# SCH_USB-Hub_2025-03-01.net
KiCad netlist of a schematic drawn in EasyEDA
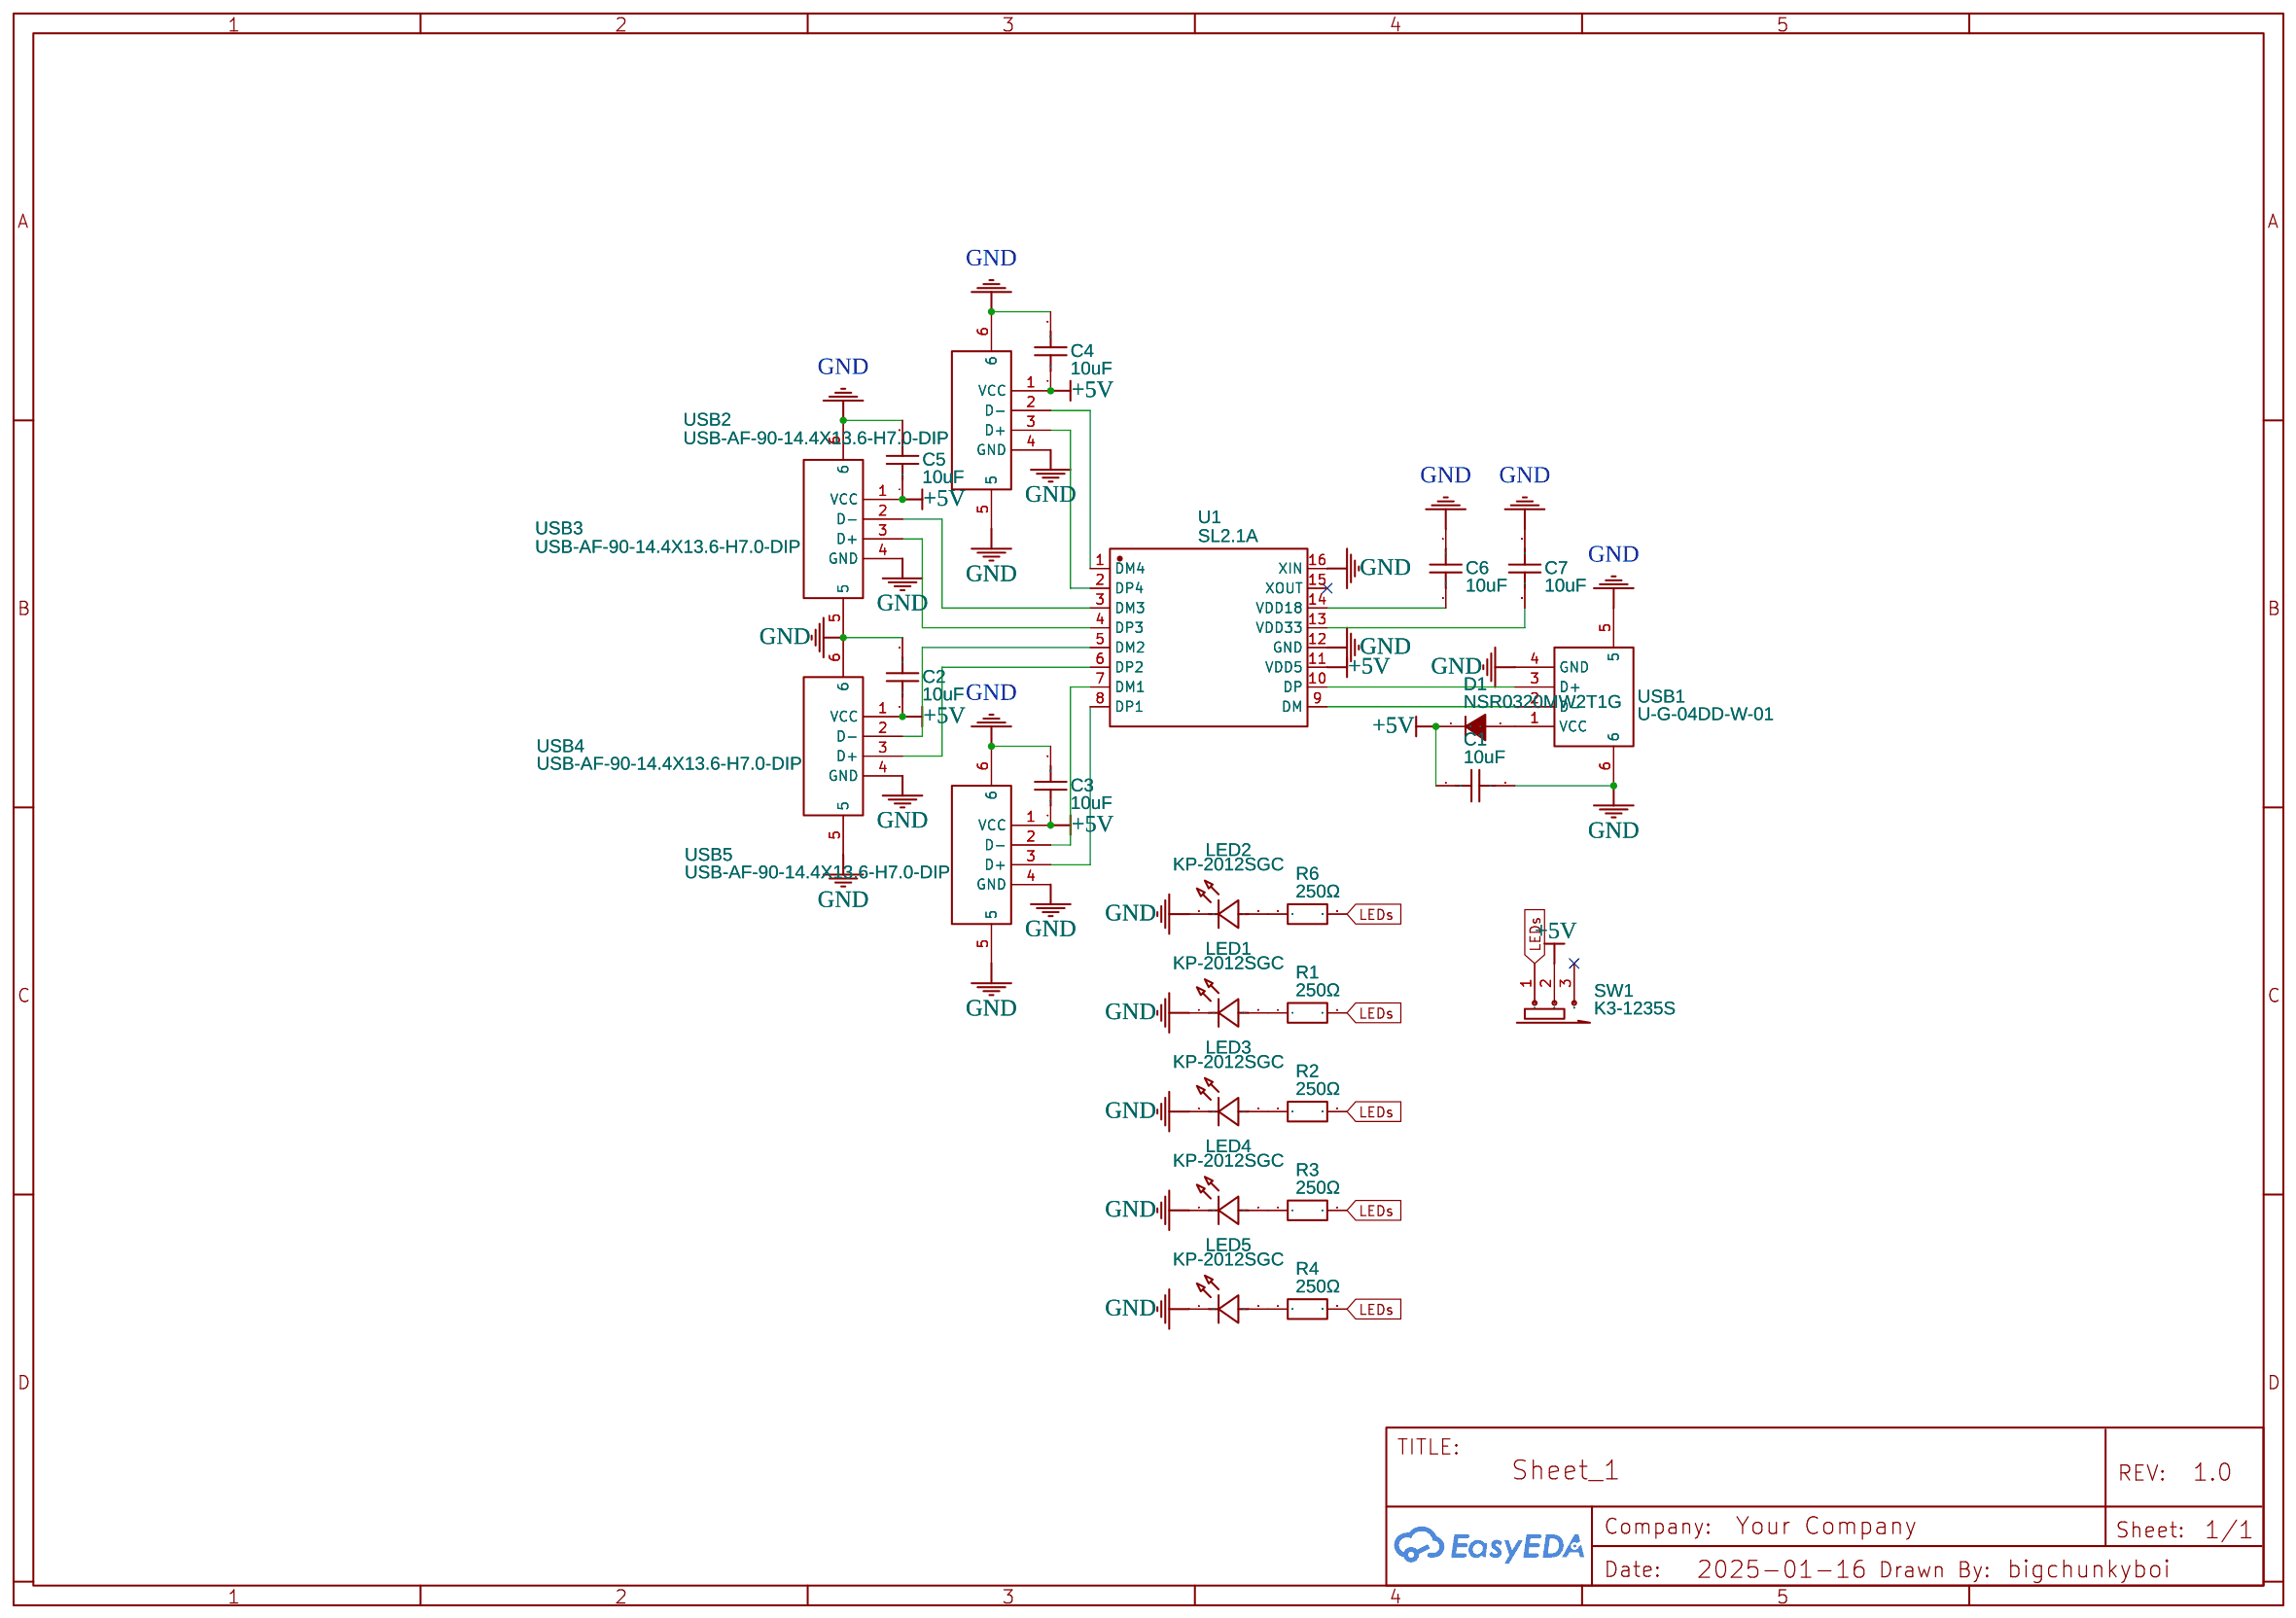
[diagram p0: schematic sheet]

(export (version "E")
  (design (tool "Eeschema 10.0.6"))
  (components
    (comp (ref "C1")
      (value "10uF")
      (fields
        (field (name "Manufacturer Part") "CL10A106KP8NNNC")
        (field (name "Manufacturer") "SAMSUNG(三星)")
      )
      (libsource (lib "") (part "CL10A106KP8NNNC_1"))
    )
    (comp (ref "C2")
      (value "10uF")
      (fields
        (field (name "Manufacturer Part") "CL10A106KP8NNNC")
        (field (name "Manufacturer") "SAMSUNG(三星)")
      )
      (libsource (lib "") (part "CL10A106KP8NNNC"))
    )
    (comp (ref "C3")
      (value "10uF")
      (fields
        (field (name "Manufacturer Part") "CL10A106KP8NNNC")
        (field (name "Manufacturer") "SAMSUNG(三星)")
      )
      (libsource (lib "") (part "CL10A106KP8NNNC"))
    )
    (comp (ref "C4")
      (value "10uF")
      (fields
        (field (name "Manufacturer Part") "CL10A106KP8NNNC")
        (field (name "Manufacturer") "SAMSUNG(三星)")
      )
      (libsource (lib "") (part "CL10A106KP8NNNC"))
    )
    (comp (ref "C5")
      (value "10uF")
      (fields
        (field (name "Manufacturer Part") "CL10A106KP8NNNC")
        (field (name "Manufacturer") "SAMSUNG(三星)")
      )
      (libsource (lib "") (part "CL10A106KP8NNNC"))
    )
    (comp (ref "C6")
      (value "10uF")
      (fields
        (field (name "Manufacturer Part") "CL10A106KP8NNNC")
        (field (name "Manufacturer") "SAMSUNG(三星)")
      )
      (libsource (lib "") (part "CL10A106KP8NNNC_2"))
    )
    (comp (ref "C7")
      (value "10uF")
      (fields
        (field (name "Manufacturer Part") "CL10A106KP8NNNC")
        (field (name "Manufacturer") "SAMSUNG(三星)")
      )
      (libsource (lib "") (part "CL10A106KP8NNNC_2"))
    )
    (comp (ref "D1")
      (value "NSR0320MW2T1G")
      (fields (field (name "Manufacturer") "onsemi(安森美)"))
      (libsource (lib "") (part "NSR0320MW2T1G"))
    )
    (comp (ref "LED1")
      (value "KP-2012SGC")
      (fields (field (name "Manufacturer") "Kingbright"))
      (libsource (lib "") (part "KP-2012SGC"))
    )
    (comp (ref "LED2")
      (value "KP-2012SGC")
      (fields (field (name "Manufacturer") "Kingbright"))
      (libsource (lib "") (part "KP-2012SGC"))
    )
    (comp (ref "LED3")
      (value "KP-2012SGC")
      (fields (field (name "Manufacturer") "Kingbright"))
      (libsource (lib "") (part "KP-2012SGC"))
    )
    (comp (ref "LED4")
      (value "KP-2012SGC")
      (fields (field (name "Manufacturer") "Kingbright"))
      (libsource (lib "") (part "KP-2012SGC"))
    )
    (comp (ref "LED5")
      (value "KP-2012SGC")
      (fields (field (name "Manufacturer") "Kingbright"))
      (libsource (lib "") (part "KP-2012SGC"))
    )
    (comp (ref "R1")
      (value "250Ω")
      (fields (field (name "Manufacturer Part") "ARG03DTC2500") (field (name "Manufacturer") "Viking(光颉)"))
      (libsource (lib "") (part "ARG03DTC2500"))
    )
    (comp (ref "R2")
      (value "250Ω")
      (fields (field (name "Manufacturer Part") "ARG03DTC2500") (field (name "Manufacturer") "Viking(光颉)"))
      (libsource (lib "") (part "ARG03DTC2500"))
    )
    (comp (ref "R3")
      (value "250Ω")
      (fields (field (name "Manufacturer Part") "ARG03DTC2500") (field (name "Manufacturer") "Viking(光颉)"))
      (libsource (lib "") (part "ARG03DTC2500"))
    )
    (comp (ref "R4")
      (value "250Ω")
      (fields (field (name "Manufacturer Part") "ARG03DTC2500") (field (name "Manufacturer") "Viking(光颉)"))
      (libsource (lib "") (part "ARG03DTC2500"))
    )
    (comp (ref "R6")
      (value "250Ω")
      (fields (field (name "Manufacturer Part") "ARG03DTC2500") (field (name "Manufacturer") "Viking(光颉)"))
      (libsource (lib "") (part "ARG03DTC2500"))
    )
    (comp (ref "SW1")
      (value "K3-1235S")
      (fields (field (name "Manufacturer Part") "K3-1235S-F1") (field (name "Manufacturer") "韩国韩荣"))
      (libsource (lib "") (part "K3-1235S"))
    )
    (comp (ref "U1")
      (value "SL2.1A")
      (fields (field (name "Manufacturer") "CoreChips(和芯润德)"))
      (libsource (lib "") (part "SL2.1A"))
    )
    (comp (ref "USB1")
      (value "U-G-04DD-W-01")
      (fields (field (name "Manufacturer Part") "U-G-O4DD-W-1") (field (name "Manufacturer") "韩国韩荣"))
      (libsource (lib "") (part "U-G-04DD-W-01"))
    )
    (comp (ref "USB2")
      (value "USB-AF-90-14.4X13.6-H7.0-DIP")
      (fields (field (name "Manufacturer Part") "903-131A1011D10100") (field (name "Manufacturer") "精拓金"))
      (libsource (lib "") (part "USB-AF-90-14.4X13.6-H7.0-DIP"))
    )
    (comp (ref "USB3")
      (value "USB-AF-90-14.4X13.6-H7.0-DIP")
      (fields (field (name "Manufacturer Part") "903-131A1011D10100") (field (name "Manufacturer") "精拓金"))
      (libsource (lib "") (part "USB-AF-90-14.4X13.6-H7.0-DIP"))
    )
    (comp (ref "USB4")
      (value "USB-AF-90-14.4X13.6-H7.0-DIP")
      (fields (field (name "Manufacturer Part") "903-131A1011D10100") (field (name "Manufacturer") "精拓金"))
      (libsource (lib "") (part "USB-AF-90-14.4X13.6-H7.0-DIP"))
    )
    (comp (ref "USB5")
      (value "USB-AF-90-14.4X13.6-H7.0-DIP")
      (fields (field (name "Manufacturer Part") "903-131A1011D10100") (field (name "Manufacturer") "精拓金"))
      (libsource (lib "") (part "USB-AF-90-14.4X13.6-H7.0-DIP"))
    )
  )
  (nets
    (net (code "1") (name "+5V") (class "Default")
      (node (ref "C1") (pin "1") (pinfunction "1_1") (pintype "unspecified"))
      (node (ref "C2") (pin "1") (pinfunction "1_1") (pintype "unspecified"))
      (node (ref "C3") (pin "1") (pinfunction "1_1") (pintype "unspecified"))
      (node (ref "C4") (pin "1") (pinfunction "1_1") (pintype "unspecified"))
      (node (ref "C5") (pin "1") (pinfunction "1_1") (pintype "unspecified"))
      (node (ref "D1") (pin "1") (pinfunction "C_1") (pintype "unspecified"))
      (node (ref "SW1") (pin "2") (pinfunction "2_2") (pintype "unspecified"))
      (node (ref "U1") (pin "11") (pinfunction "VDD5_11") (pintype "unspecified"))
      (node (ref "USB2") (pin "1") (pinfunction "VCC_1") (pintype "unspecified"))
      (node (ref "USB3") (pin "1") (pinfunction "VCC_1") (pintype "unspecified"))
      (node (ref "USB4") (pin "1") (pinfunction "VCC_1") (pintype "unspecified"))
      (node (ref "USB5") (pin "1") (pinfunction "VCC_1") (pintype "unspecified"))
    )
    (net (code "2") (name "GND") (class "Default")
      (node (ref "C1") (pin "2") (pinfunction "2_2") (pintype "unspecified"))
      (node (ref "C2") (pin "2") (pinfunction "2_2") (pintype "unspecified"))
      (node (ref "C3") (pin "2") (pinfunction "2_2") (pintype "unspecified"))
      (node (ref "C4") (pin "2") (pinfunction "2_2") (pintype "unspecified"))
      (node (ref "C5") (pin "2") (pinfunction "2_2") (pintype "unspecified"))
      (node (ref "C6") (pin "1") (pinfunction "1_1") (pintype "unspecified"))
      (node (ref "C7") (pin "1") (pinfunction "1_1") (pintype "unspecified"))
      (node (ref "LED1") (pin "1") (pinfunction "K_1") (pintype "unspecified"))
      (node (ref "LED2") (pin "1") (pinfunction "K_1") (pintype "unspecified"))
      (node (ref "LED3") (pin "1") (pinfunction "K_1") (pintype "unspecified"))
      (node (ref "LED4") (pin "1") (pinfunction "K_1") (pintype "unspecified"))
      (node (ref "LED5") (pin "1") (pinfunction "K_1") (pintype "unspecified"))
      (node (ref "U1") (pin "12") (pinfunction "GND_12") (pintype "unspecified"))
      (node (ref "U1") (pin "16") (pinfunction "XIN_16") (pintype "unspecified"))
      (node (ref "USB1") (pin "4") (pinfunction "GND_4") (pintype "unspecified"))
      (node (ref "USB1") (pin "5") (pinfunction "5_5") (pintype "unspecified"))
      (node (ref "USB1") (pin "6") (pinfunction "6_6") (pintype "unspecified"))
      (node (ref "USB2") (pin "4") (pinfunction "GND_4") (pintype "unspecified"))
      (node (ref "USB2") (pin "5") (pinfunction "5_5") (pintype "unspecified"))
      (node (ref "USB2") (pin "6") (pinfunction "6_6") (pintype "unspecified"))
      (node (ref "USB3") (pin "4") (pinfunction "GND_4") (pintype "unspecified"))
      (node (ref "USB3") (pin "5") (pinfunction "5_5") (pintype "unspecified"))
      (node (ref "USB3") (pin "6") (pinfunction "6_6") (pintype "unspecified"))
      (node (ref "USB4") (pin "4") (pinfunction "GND_4") (pintype "unspecified"))
      (node (ref "USB4") (pin "5") (pinfunction "5_5") (pintype "unspecified"))
      (node (ref "USB4") (pin "6") (pinfunction "6_6") (pintype "unspecified"))
      (node (ref "USB5") (pin "4") (pinfunction "GND_4") (pintype "unspecified"))
      (node (ref "USB5") (pin "5") (pinfunction "5_5") (pintype "unspecified"))
      (node (ref "USB5") (pin "6") (pinfunction "6_6") (pintype "unspecified"))
    )
    (net (code "3") (name "LEDs") (class "Default")
      (node (ref "R1") (pin "2") (pinfunction "2_2") (pintype "unspecified"))
      (node (ref "R2") (pin "2") (pinfunction "2_2") (pintype "unspecified"))
      (node (ref "R3") (pin "2") (pinfunction "2_2") (pintype "unspecified"))
      (node (ref "R4") (pin "2") (pinfunction "2_2") (pintype "unspecified"))
      (node (ref "R6") (pin "2") (pinfunction "2_2") (pintype "unspecified"))
      (node (ref "SW1") (pin "1") (pinfunction "1_1") (pintype "unspecified"))
    )
    (net (code "4") (name "Net-(D1-A)") (class "Default")
      (node (ref "D1") (pin "2") (pinfunction "A_2") (pintype "unspecified"))
      (node (ref "USB1") (pin "1") (pinfunction "VCC_1") (pintype "unspecified"))
    )
    (net (code "5") (name "Net-(LED1-A)") (class "Default")
      (node (ref "LED1") (pin "2") (pinfunction "A_2") (pintype "unspecified"))
      (node (ref "R1") (pin "1") (pinfunction "1_1") (pintype "unspecified"))
    )
    (net (code "6") (name "Net-(LED2-A)") (class "Default")
      (node (ref "LED2") (pin "2") (pinfunction "A_2") (pintype "unspecified"))
      (node (ref "R6") (pin "1") (pinfunction "1_1") (pintype "unspecified"))
    )
    (net (code "7") (name "Net-(LED3-A)") (class "Default")
      (node (ref "LED3") (pin "2") (pinfunction "A_2") (pintype "unspecified"))
      (node (ref "R2") (pin "1") (pinfunction "1_1") (pintype "unspecified"))
    )
    (net (code "8") (name "Net-(LED4-A)") (class "Default")
      (node (ref "LED4") (pin "2") (pinfunction "A_2") (pintype "unspecified"))
      (node (ref "R3") (pin "1") (pinfunction "1_1") (pintype "unspecified"))
    )
    (net (code "9") (name "Net-(LED5-A)") (class "Default")
      (node (ref "LED5") (pin "2") (pinfunction "A_2") (pintype "unspecified"))
      (node (ref "R4") (pin "1") (pinfunction "1_1") (pintype "unspecified"))
    )
    (net (code "10") (name "Net-(U1-DM)") (class "Default")
      (node (ref "U1") (pin "9") (pinfunction "DM_9") (pintype "unspecified"))
      (node (ref "USB1") (pin "2") (pinfunction "D-_2") (pintype "unspecified"))
    )
    (net (code "11") (name "Net-(U1-DM1)") (class "Default")
      (node (ref "U1") (pin "7") (pinfunction "DM1_7") (pintype "unspecified"))
      (node (ref "USB5") (pin "2") (pinfunction "D-_2") (pintype "unspecified"))
    )
    (net (code "12") (name "Net-(U1-DM2)") (class "Default")
      (node (ref "U1") (pin "5") (pinfunction "DM2_5") (pintype "unspecified"))
      (node (ref "USB4") (pin "2") (pinfunction "D-_2") (pintype "unspecified"))
    )
    (net (code "13") (name "Net-(U1-DM3)") (class "Default")
      (node (ref "U1") (pin "3") (pinfunction "DM3_3") (pintype "unspecified"))
      (node (ref "USB3") (pin "2") (pinfunction "D-_2") (pintype "unspecified"))
    )
    (net (code "14") (name "Net-(U1-DM4)") (class "Default")
      (node (ref "U1") (pin "1") (pinfunction "DM4_1") (pintype "unspecified"))
      (node (ref "USB2") (pin "2") (pinfunction "D-_2") (pintype "unspecified"))
    )
    (net (code "15") (name "Net-(U1-DP)") (class "Default")
      (node (ref "U1") (pin "10") (pinfunction "DP_10") (pintype "unspecified"))
      (node (ref "USB1") (pin "3") (pinfunction "D+_3") (pintype "unspecified"))
    )
    (net (code "16") (name "Net-(U1-DP1)") (class "Default")
      (node (ref "U1") (pin "8") (pinfunction "DP1_8") (pintype "unspecified"))
      (node (ref "USB5") (pin "3") (pinfunction "D+_3") (pintype "unspecified"))
    )
    (net (code "17") (name "Net-(U1-DP2)") (class "Default")
      (node (ref "U1") (pin "6") (pinfunction "DP2_6") (pintype "unspecified"))
      (node (ref "USB4") (pin "3") (pinfunction "D+_3") (pintype "unspecified"))
    )
    (net (code "18") (name "Net-(U1-DP3)") (class "Default")
      (node (ref "U1") (pin "4") (pinfunction "DP3_4") (pintype "unspecified"))
      (node (ref "USB3") (pin "3") (pinfunction "D+_3") (pintype "unspecified"))
    )
    (net (code "19") (name "Net-(U1-DP4)") (class "Default")
      (node (ref "U1") (pin "2") (pinfunction "DP4_2") (pintype "unspecified"))
      (node (ref "USB2") (pin "3") (pinfunction "D+_3") (pintype "unspecified"))
    )
    (net (code "20") (name "Net-(U1-VDD18)") (class "Default")
      (node (ref "C6") (pin "2") (pinfunction "2_2") (pintype "unspecified"))
      (node (ref "U1") (pin "14") (pinfunction "VDD18_14") (pintype "unspecified"))
    )
    (net (code "21") (name "Net-(U1-VDD33)") (class "Default")
      (node (ref "C7") (pin "2") (pinfunction "2_2") (pintype "unspecified"))
      (node (ref "U1") (pin "13") (pinfunction "VDD33_13") (pintype "unspecified"))
    )
    (net (code "22") (name "unconnected-(SW1-Pad3)") (class "Default")
      (node (ref "SW1") (pin "3") (pinfunction "3_3") (pintype "unspecified+no_connect"))
    )
    (net (code "23") (name "unconnected-(U1-XOUT-Pad15)") (class "Default")
      (node (ref "U1") (pin "15") (pinfunction "XOUT_15") (pintype "unspecified+no_connect"))
    )
  )
)
